# AIRZAI_BASE_BD_REVA_Sheet2.net
KiCad netlist of a schematic drawn in Altium Designer
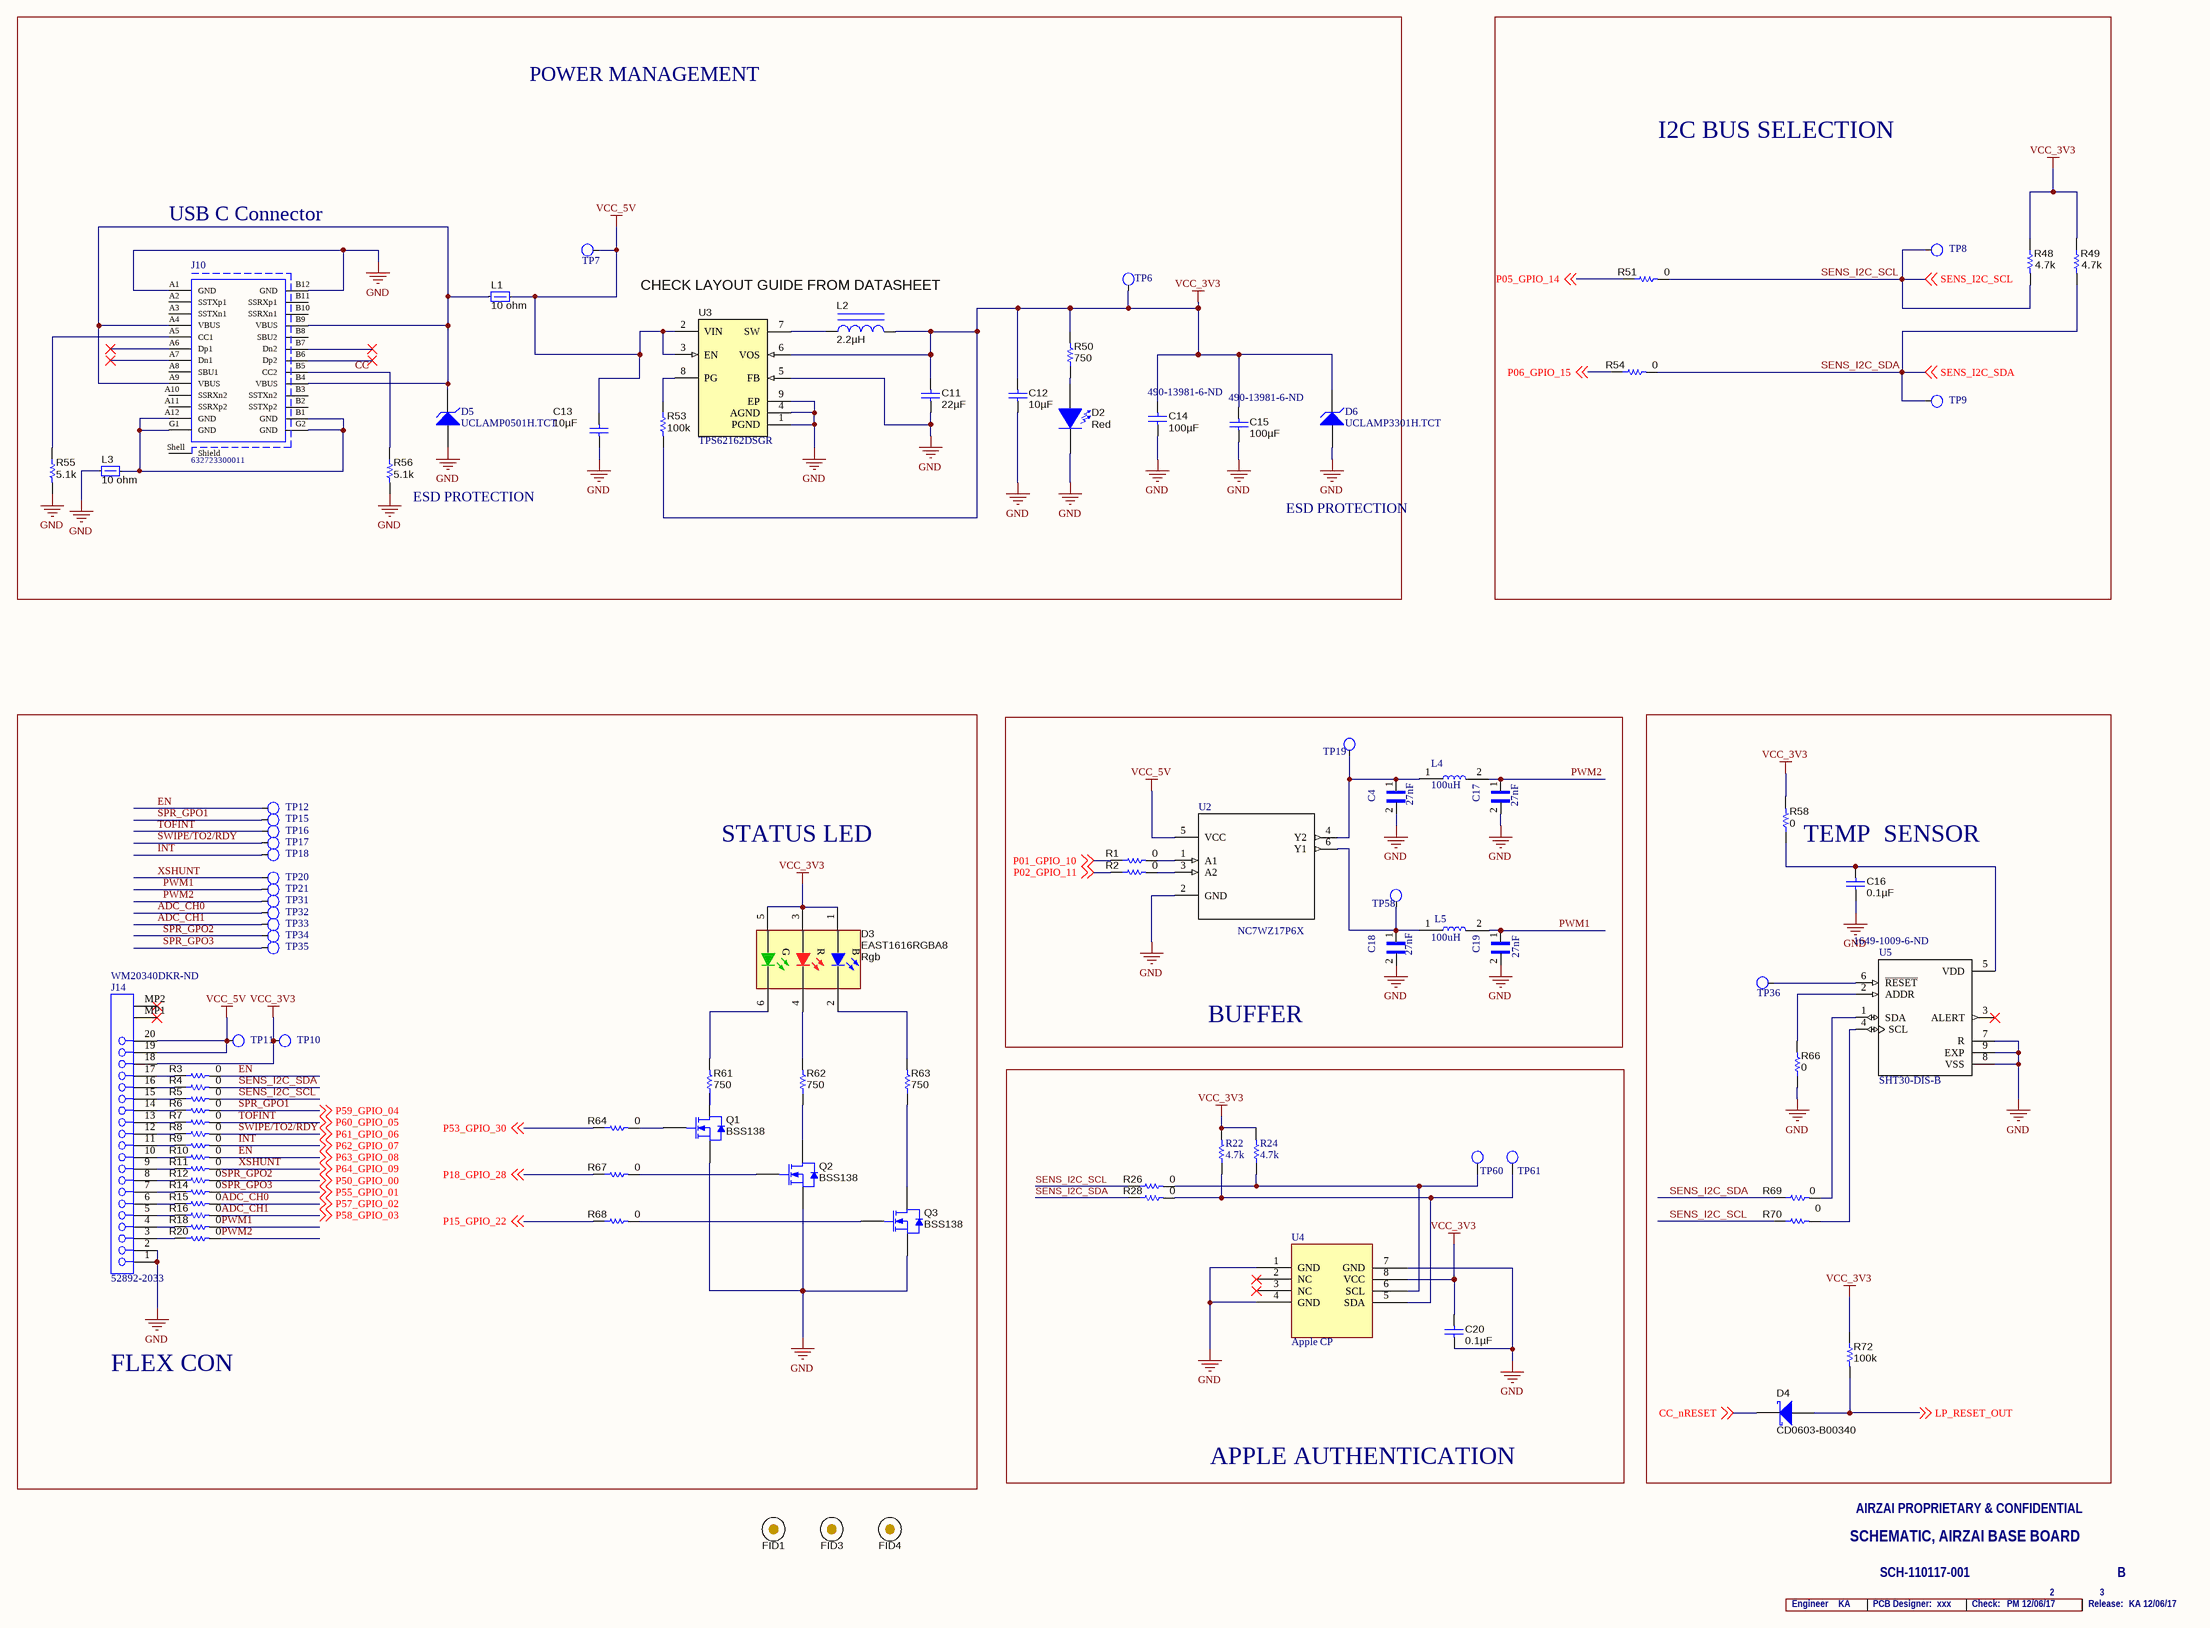
[diagram p0: AIRZAI_BASE_BD_REVA Sheet2.SchDoc]

(export (version "E")
  (design (tool "Eeschema 10.0.6"))
  (components
    (comp (ref "C4")
      (value "27nF")
      (footprint "1206CAP")
      (description "1206 27 nF 50 V Â±5% Tolerance C0G SMT Multilayer Ceramic Capacitor")
      (fields (field (name "MF") "Murata Electronics") (field (name "MP") "GRM3195C1H273JA01D"))
      (libsource (lib "GRM3195C1H273JA01D") (part "GRM3195C1H273JA01D"))
    )
    (comp (ref "C11")
      (value "C2012X5R1C226K125AC")
      (footprint "0805_HV")
      (description "CAP, CERM, 22 µF, 16 V, +/- 10%, X5R, 0805")
      (fields
        (field (name "VALUEDISPLAYED") "22µF")
        (field (name "MANUFACTURER") "TDK")
        (field (name "PUBLISHER") "Texas Instruments")
      )
      (libsource (lib "Capacitor_Ceramic") (part "C2012X5R1C226K125AC"))
    )
    (comp (ref "C12")
      (value "GRM21BR61A106KE19L")
      (footprint "0805_HV")
      (description "CAP, CERM, 10 µF, 10 V, +/- 10%, X5R, 0805")
      (fields
        (field (name "VALUEDISPLAYED") "10µF")
        (field (name "MANUFACTURER") "MuRata")
        (field (name "PUBLISHER") "Texas Instruments")
      )
      (libsource (lib "Capacitor_Ceramic") (part "GRM21BR61A106KE19L"))
    )
    (comp (ref "C13")
      (value "GRM21BR61A106KE19L")
      (footprint "0805_HV")
      (description "CAP, CERM, 10 µF, 10 V, +/- 10%, X5R, 0805")
      (fields
        (field (name "VALUEDISPLAYED") "10µF")
        (field (name "MANUFACTURER") "MuRata")
        (field (name "PUBLISHER") "Texas Instruments")
      )
      (libsource (lib "Capacitor_Ceramic") (part "GRM21BR61A106KE19L"))
    )
    (comp (ref "C14")
      (value "GRM31CR60J107ME39L")
      (footprint "1206_180")
      (description "CAP, CERM, 100 µF, 6.3 V, +/- 20%, X5R, 1206")
      (fields
        (field (name "VALUEDISPLAYED") "100µF")
        (field (name "MANUFACTURER") "MuRata")
        (field (name "SUPPLIER PART NUMBER 3") "490-13981-6-ND")
        (field (name "PUBLISHER") "Texas Instruments")
      )
      (libsource (lib "Capacitor_Ceramic") (part "GRM31CR60J107ME39L"))
    )
    (comp (ref "C15")
      (value "GRM31CR60J107ME39L")
      (footprint "1206_180")
      (description "CAP, CERM, 100 µF, 6.3 V, +/- 20%, X5R, 1206")
      (fields
        (field (name "VALUEDISPLAYED") "100µF")
        (field (name "MANUFACTURER") "MuRata")
        (field (name "SUPPLIER PART NUMBER 3") "490-13981-6-ND")
        (field (name "PUBLISHER") "Texas Instruments")
      )
      (libsource (lib "Capacitor_Ceramic") (part "GRM31CR60J107ME39L"))
    )
    (comp (ref "C16")
      (value "GRM155R61A104KA01D")
      (footprint "0402")
      (description "CAP, CERM, 0.1 µF, 10 V, +/- 10%, X5R, 0402")
      (fields
        (field (name "VALUEDISPLAYED") "0.1µF")
        (field (name "MANUFACTURER") "MuRata")
        (field (name "PUBLISHER") "Texas Instruments")
      )
      (libsource (lib "Capacitor_Ceramic") (part "GRM155R61A104KA01D"))
    )
    (comp (ref "C17")
      (value "27nF")
      (footprint "1206CAP")
      (description "1206 27 nF 50 V Â±5% Tolerance C0G SMT Multilayer Ceramic Capacitor")
      (fields (field (name "MF") "Murata Electronics") (field (name "MP") "GRM3195C1H273JA01D"))
      (libsource (lib "GRM3195C1H273JA01D") (part "GRM3195C1H273JA01D"))
    )
    (comp (ref "C18")
      (value "27nF")
      (footprint "1206CAP")
      (description "1206 27 nF 50 V Â±5% Tolerance C0G SMT Multilayer Ceramic Capacitor")
      (fields (field (name "MF") "Murata Electronics") (field (name "MP") "GRM3195C1H273JA01D"))
      (libsource (lib "GRM3195C1H273JA01D") (part "GRM3195C1H273JA01D"))
    )
    (comp (ref "C19")
      (value "27nF")
      (footprint "1206CAP")
      (description "1206 27 nF 50 V Â±5% Tolerance C0G SMT Multilayer Ceramic Capacitor")
      (fields (field (name "MF") "Murata Electronics") (field (name "MP") "GRM3195C1H273JA01D"))
      (libsource (lib "GRM3195C1H273JA01D") (part "GRM3195C1H273JA01D"))
    )
    (comp (ref "C20")
      (value "C1005X5R1A104K050BA")
      (footprint "SM0402_BTD.1SM_ACT_H55_CAP_WSS")
      (description "CAP, CERM, 0.1 µF, 10 V, +/- 10%, X5R, 0402")
      (fields
        (field (name "MANUFACTURER") "TDK")
        (field (name "VALUEDISPLAYED") "0.1µF")
        (field (name "PUBLISHER") "Texas Instruments")
      )
      (libsource (lib "AIRZAI_MBD_REVB2") (part "C1005X5R1A104K050BA"))
    )
    (comp (ref "D2")
      (value "Red")
      (footprint "SML-31_Red")
      (description "LED, Red, SMD")
      (fields
        (field (name "MANUFACTURER") "Rohm")
        (field (name "PARTNUMBER") "SML-311UTT86")
        (field (name "PUBLISHER") "Texas Instruments")
      )
      (libsource (lib "LED") (part "SML-311UTT86"))
    )
    (comp (ref "D3")
      (value "EAST1616RGBA8")
      (footprint "EAST1616_RGB")
      (description "LED, Rgb, SMD")
      (fields
        (field (name "ALTIUM_VALUE") "Rgb")
        (field (name "MANUFACTURER") "Everlight")
        (field (name "SYMBOLCREATOR") "Altium")
        (field (name "PUBLISHER") "Texas Instruments")
      )
      (libsource (lib "LED") (part "EAST1616RGBA8"))
    )
    (comp (ref "D4")
      (value "CD0603-B00340")
      (footprint "Diode_0603")
      (description "Diode, Schottky, 45 V, 0.03 A, 0603 Diode")
      (fields (field (name "MANUFACTURER") "Bourns") (field (name "PUBLISHER") "Texas Instruments"))
      (libsource (lib "Diode") (part "CD0603-B00340"))
    )
    (comp (ref "D5")
      (value "UCLAMP0501H.TCT")
      (footprint "SOD-523")
      (description "TVS DIODE 5V 12.5V SOD523")
      (fields (field (name "MANUFACTURER") "Semtech"))
      (libsource (lib "AIRZAI_BASE_BD_REVA") (part "UCLAMP0501H.TCT"))
    )
    (comp (ref "D6")
      (value "UCLAMP3301H.TCT")
      (footprint "SOD-523")
      (description "TVS DIODE 3.3V 8V SOD523")
      (fields (field (name "MANUFACTURER") "Semtech"))
      (libsource (lib "AIRZAI_BASE_BD_REVA") (part "UCLAMP3301H.TCT"))
    )
    (comp (ref "FID1")
      (value "Fiducial")
      (footprint "Fiducial10-20")
      (description "Fiducial mark.  There is nothing to buy or mount.")
      (fields (field (name "SYMBOLCREATOR") "codlsc") (field (name "PUBLISHER") "Texas Instruments"))
      (libsource (lib "MiscParts") (part "Fiducial"))
    )
    (comp (ref "FID3")
      (value "Fiducial")
      (footprint "Fiducial10-20")
      (description "Fiducial mark.  There is nothing to buy or mount.")
      (fields (field (name "SYMBOLCREATOR") "codlsc") (field (name "PUBLISHER") "Texas Instruments"))
      (libsource (lib "MiscParts") (part "Fiducial"))
    )
    (comp (ref "FID4")
      (value "Fiducial")
      (footprint "Fiducial10-20")
      (description "Fiducial mark.  There is nothing to buy or mount.")
      (fields (field (name "SYMBOLCREATOR") "codlsc") (field (name "PUBLISHER") "Texas Instruments"))
      (libsource (lib "MiscParts") (part "Fiducial"))
    )
    (comp (ref "J10")
      (value "632723300011")
      (footprint "632723300011")
      (description "USB 3.1 Type C Receptacle WR-COM, Horizontal, SMT / THT")
      (fields (field (name "PUBLISHER") "Wurth Elektronik"))
      (libsource (lib "Altium_WR-COM_USB-Connectors (rev18b)") (part "632723300011"))
    )
    (comp (ref "J14")
      (value "52892-2033")
      (footprint "MOLX-52892-2033")
      (fields (field (name "MANUFACTURER") "Molex") (field (name "SUPPLIER PART NUMBER 1") "WM20340DKR-ND"))
      (libsource (lib "Altium Content Vault") (part "MOLX-52892-2033"))
    )
    (comp (ref "L1")
      (value "10 ohm")
      (footprint "0402")
      (description "Ferrite Bead, 10 ohm @ 100 MHz, 1 A, 0402")
      (fields
        (field (name "PARTNUMBER") "BLM15AG100SN1D")
        (field (name "MANUFACTURER") "MuRata")
        (field (name "PUBLISHER") "Texas Instruments")
      )
      (libsource (lib "FerriteBead") (part "BLM15AG100SN1D"))
    )
    (comp (ref "L2")
      (value "BRC2012T2R2MD")
      (footprint "0805_HV")
      (description "Inductor, Wirewound, 2.2 µH, 1 A, 0.143 ohm, SMD")
      (fields
        (field (name "VALUEDISPLAYED") "2.2µH")
        (field (name "MANUFACTURER") "Taiyo Yuden")
        (field (name "PUBLISHER") "Texas Instruments")
      )
      (libsource (lib "Inductor_Other") (part "BRC2012T2R2MD"))
    )
    (comp (ref "L3")
      (value "10 ohm")
      (footprint "0402")
      (description "Ferrite Bead, 10 ohm @ 100 MHz, 1 A, 0402")
      (fields
        (field (name "PARTNUMBER") "BLM15AG100SN1D")
        (field (name "MANUFACTURER") "MuRata")
        (field (name "PUBLISHER") "Texas Instruments")
      )
      (libsource (lib "") (part "BLM15AG100SN1D_1"))
    )
    (comp (ref "L4")
      (value "100uH")
      (footprint "0805_Inductor")
      (description "Fixed Ind 100uh 2ma 3.1 Ohm Smd")
      (fields (field (name "MP") "MLF2012C101KTD25") (field (name "MF") "TDK"))
      (libsource (lib "MLF2012C101KTD25") (part "MLF2012C101KTD25"))
    )
    (comp (ref "L5")
      (value "100uH")
      (footprint "0805_Inductor")
      (description "Fixed Ind 100uh 2ma 3.1 Ohm Smd")
      (fields (field (name "MP") "MLF2012C101KTD25") (field (name "MF") "TDK"))
      (libsource (lib "MLF2012C101KTD25") (part "MLF2012C101KTD25"))
    )
    (comp (ref "Q1")
      (value "BSS138")
      (footprint "SOT-23")
      (description "MOSFET, N-CH, 50 V, 0.22 A, SOT-23")
      (fields
        (field (name "MANUFACTURER") "Fairchild Semiconductor")
        (field (name "PUBLISHER") "Texas Instruments")
      )
      (libsource (lib "FETs") (part "BSS138"))
    )
    (comp (ref "Q2")
      (value "BSS138")
      (footprint "SOT-23")
      (description "MOSFET, N-CH, 50 V, 0.22 A, SOT-23")
      (fields
        (field (name "MANUFACTURER") "Fairchild Semiconductor")
        (field (name "PUBLISHER") "Texas Instruments")
      )
      (libsource (lib "FETs") (part "BSS138"))
    )
    (comp (ref "Q3")
      (value "BSS138")
      (footprint "SOT-23")
      (description "MOSFET, N-CH, 50 V, 0.22 A, SOT-23")
      (fields
        (field (name "MANUFACTURER") "Fairchild Semiconductor")
        (field (name "PUBLISHER") "Texas Instruments")
      )
      (libsource (lib "FETs") (part "BSS138"))
    )
    (comp (ref "R1")
      (value "ERJ-2GE0R00X")
      (footprint "0402")
      (description "RES, 0, 5%, 0.063 W, 0402")
      (fields
        (field (name "VALUEDISPLAYED") "0")
        (field (name "MANUFACTURER") "Panasonic")
        (field (name "DIGI-KEY_PART_NUMBER") "P0.0JCT-ND")
        (field (name "PUBLISHER") "Texas Instruments")
      )
      (libsource (lib "Resistor_0402") (part "ERJ-2GE0R00X"))
    )
    (comp (ref "R2")
      (value "ERJ-2GE0R00X")
      (footprint "0402")
      (description "RES, 0, 5%, 0.063 W, 0402")
      (fields
        (field (name "VALUEDISPLAYED") "0")
        (field (name "MANUFACTURER") "Panasonic")
        (field (name "DIGI-KEY_PART_NUMBER") "P0.0JCT-ND")
        (field (name "PUBLISHER") "Texas Instruments")
      )
      (libsource (lib "Resistor_0402") (part "ERJ-2GE0R00X"))
    )
    (comp (ref "R3")
      (value "ERJ-2GE0R00X")
      (footprint "0402")
      (description "RES, 0, 5%, 0.063 W, 0402")
      (fields
        (field (name "VALUEDISPLAYED") "0")
        (field (name "MANUFACTURER") "Panasonic")
        (field (name "PUBLISHER") "Texas Instruments")
      )
      (libsource (lib "Resistor_0402") (part "ERJ-2GE0R00X"))
    )
    (comp (ref "R4")
      (value "ERJ-2GE0R00X")
      (footprint "0402")
      (description "RES, 0, 5%, 0.063 W, 0402")
      (fields
        (field (name "VALUEDISPLAYED") "0")
        (field (name "MANUFACTURER") "Panasonic")
        (field (name "PUBLISHER") "Texas Instruments")
      )
      (libsource (lib "Resistor_0402") (part "ERJ-2GE0R00X"))
    )
    (comp (ref "R5")
      (value "ERJ-2GE0R00X")
      (footprint "0402")
      (description "RES, 0, 5%, 0.063 W, 0402")
      (fields
        (field (name "VALUEDISPLAYED") "0")
        (field (name "MANUFACTURER") "Panasonic")
        (field (name "PUBLISHER") "Texas Instruments")
      )
      (libsource (lib "Resistor_0402") (part "ERJ-2GE0R00X"))
    )
    (comp (ref "R6")
      (value "ERJ-2GE0R00X")
      (footprint "0402")
      (description "RES, 0, 5%, 0.063 W, 0402")
      (fields
        (field (name "VALUEDISPLAYED") "0")
        (field (name "MANUFACTURER") "Panasonic")
        (field (name "PUBLISHER") "Texas Instruments")
      )
      (libsource (lib "Resistor_0402") (part "ERJ-2GE0R00X"))
    )
    (comp (ref "R7")
      (value "ERJ-2GE0R00X")
      (footprint "0402")
      (description "RES, 0, 5%, 0.063 W, 0402")
      (fields
        (field (name "VALUEDISPLAYED") "0")
        (field (name "MANUFACTURER") "Panasonic")
        (field (name "PUBLISHER") "Texas Instruments")
      )
      (libsource (lib "Resistor_0402") (part "ERJ-2GE0R00X"))
    )
    (comp (ref "R8")
      (value "ERJ-2GE0R00X")
      (footprint "0402")
      (description "RES, 0, 5%, 0.063 W, 0402")
      (fields
        (field (name "VALUEDISPLAYED") "0")
        (field (name "MANUFACTURER") "Panasonic")
        (field (name "PUBLISHER") "Texas Instruments")
      )
      (libsource (lib "Resistor_0402") (part "ERJ-2GE0R00X"))
    )
    (comp (ref "R9")
      (value "ERJ-2GE0R00X")
      (footprint "0402")
      (description "RES, 0, 5%, 0.063 W, 0402")
      (fields
        (field (name "VALUEDISPLAYED") "0")
        (field (name "MANUFACTURER") "Panasonic")
        (field (name "PUBLISHER") "Texas Instruments")
      )
      (libsource (lib "Resistor_0402") (part "ERJ-2GE0R00X"))
    )
    (comp (ref "R10")
      (value "ERJ-2GE0R00X")
      (footprint "0402")
      (description "RES, 0, 5%, 0.063 W, 0402")
      (fields
        (field (name "VALUEDISPLAYED") "0")
        (field (name "MANUFACTURER") "Panasonic")
        (field (name "PUBLISHER") "Texas Instruments")
      )
      (libsource (lib "Resistor_0402") (part "ERJ-2GE0R00X"))
    )
    (comp (ref "R11")
      (value "ERJ-2GE0R00X")
      (footprint "0402")
      (description "RES, 0, 5%, 0.063 W, 0402")
      (fields
        (field (name "VALUEDISPLAYED") "0")
        (field (name "MANUFACTURER") "Panasonic")
        (field (name "PUBLISHER") "Texas Instruments")
      )
      (libsource (lib "Resistor_0402") (part "ERJ-2GE0R00X"))
    )
    (comp (ref "R12")
      (value "ERJ-2GE0R00X")
      (footprint "0402")
      (description "RES, 0, 5%, 0.063 W, 0402")
      (fields
        (field (name "VALUEDISPLAYED") "0")
        (field (name "MANUFACTURER") "Panasonic")
        (field (name "PUBLISHER") "Texas Instruments")
      )
      (libsource (lib "Resistor_0402") (part "ERJ-2GE0R00X"))
    )
    (comp (ref "R14")
      (value "ERJ-2GE0R00X")
      (footprint "0402")
      (description "RES, 0, 5%, 0.063 W, 0402")
      (fields
        (field (name "VALUEDISPLAYED") "0")
        (field (name "MANUFACTURER") "Panasonic")
        (field (name "PUBLISHER") "Texas Instruments")
      )
      (libsource (lib "Resistor_0402") (part "ERJ-2GE0R00X"))
    )
    (comp (ref "R15")
      (value "ERJ-2GE0R00X")
      (footprint "0402")
      (description "RES, 0, 5%, 0.063 W, 0402")
      (fields
        (field (name "VALUEDISPLAYED") "0")
        (field (name "MANUFACTURER") "Panasonic")
        (field (name "PUBLISHER") "Texas Instruments")
      )
      (libsource (lib "Resistor_0402") (part "ERJ-2GE0R00X"))
    )
    (comp (ref "R16")
      (value "ERJ-2GE0R00X")
      (footprint "0402")
      (description "RES, 0, 5%, 0.063 W, 0402")
      (fields
        (field (name "VALUEDISPLAYED") "0")
        (field (name "MANUFACTURER") "Panasonic")
        (field (name "PUBLISHER") "Texas Instruments")
      )
      (libsource (lib "Resistor_0402") (part "ERJ-2GE0R00X"))
    )
    (comp (ref "R18")
      (value "ERJ-2GE0R00X")
      (footprint "0402")
      (description "RES, 0, 5%, 0.063 W, 0402")
      (fields
        (field (name "VALUEDISPLAYED") "0")
        (field (name "MANUFACTURER") "Panasonic")
        (field (name "PUBLISHER") "Texas Instruments")
      )
      (libsource (lib "Resistor_0402") (part "ERJ-2GE0R00X"))
    )
    (comp (ref "R20")
      (value "ERJ-2GE0R00X")
      (footprint "0402")
      (description "RES, 0, 5%, 0.063 W, 0402")
      (fields
        (field (name "VALUEDISPLAYED") "0")
        (field (name "MANUFACTURER") "Panasonic")
        (field (name "PUBLISHER") "Texas Instruments")
      )
      (libsource (lib "Resistor_0402") (part "ERJ-2GE0R00X"))
    )
    (comp (ref "R22")
      (value "RMCF0402JT4K70")
      (footprint "0402")
      (description "Chip Resistor, 4.7 KOhm, +/- 5%, 0.063 W, -55 to 155 degC, 0402 (1005 Metric), RoHS, Tape and Reel")
      (fields
        (field (name "MANUFACTURER") "Stackpole-Electronics-Inc.")
        (field (name "TOLERANCE") "±5%")
        (field (name "RESISTANCE (OHMS)") "4.7k")
      )
      (libsource (lib "AIRZAI_BASE_BD_REVA") (part "RES-2"))
    )
    (comp (ref "R24")
      (value "RMCF0402JT4K70")
      (footprint "0402")
      (description "Chip Resistor, 4.7 KOhm, +/- 5%, 0.063 W, -55 to 155 degC, 0402 (1005 Metric), RoHS, Tape and Reel")
      (fields
        (field (name "MANUFACTURER") "Stackpole-Electronics-Inc.")
        (field (name "TOLERANCE") "±5%")
        (field (name "RESISTANCE (OHMS)") "4.7k")
      )
      (libsource (lib "AIRZAI_BASE_BD_REVA") (part "RES-2"))
    )
    (comp (ref "R26")
      (value "ERJ-2GE0R00X")
      (footprint "0402")
      (description "RES, 0, 5%, 0.063 W, 0402")
      (fields
        (field (name "VALUEDISPLAYED") "0")
        (field (name "MANUFACTURER") "Panasonic")
        (field (name "DIGI-KEY_PART_NUMBER") "P0.0JCT-ND")
        (field (name "PUBLISHER") "Texas Instruments")
      )
      (libsource (lib "Resistor_0402") (part "ERJ-2GE0R00X"))
    )
    (comp (ref "R28")
      (value "ERJ-2GE0R00X")
      (footprint "0402")
      (description "RES, 0, 5%, 0.063 W, 0402")
      (fields
        (field (name "VALUEDISPLAYED") "0")
        (field (name "MANUFACTURER") "Panasonic")
        (field (name "DIGI-KEY_PART_NUMBER") "P0.0JCT-ND")
        (field (name "PUBLISHER") "Texas Instruments")
      )
      (libsource (lib "Resistor_0402") (part "ERJ-2GE0R00X"))
    )
    (comp (ref "R48")
      (value "4.7k")
      (footprint "0402")
      (description "RES SMD 4.7K OHM 1% 1/16W 0402")
      (fields
        (field (name "MANUFACTURER") "Yageo")
        (field (name "MANUFACTURER PART NUMBER") "RC0402FR-074K7L")
      )
      (libsource (lib "Resistor_0402") (part "CRCW04023K30JNED"))
    )
    (comp (ref "R49")
      (value "4.7k")
      (footprint "0402")
      (description "RES SMD 4.7K OHM 1% 1/16W 0402")
      (fields
        (field (name "MANUFACTURER") "Yageo")
        (field (name "MANUFACTURER PART NUMBER") "RC0402FR-074K7L")
      )
      (libsource (lib "Resistor_0402") (part "CRCW04023K30JNED"))
    )
    (comp (ref "R50")
      (value "RC0603JR-07750RL")
      (footprint "0603")
      (description "RES, 750, 5%, 0.1 W, 0603")
      (fields
        (field (name "VALUEDISPLAYED") "750")
        (field (name "MANUFACTURER") "Yageo America")
        (field (name "PUBLISHER") "Texas Instruments")
      )
      (libsource (lib "Resistor_0603") (part "RC0603JR-07750RL"))
    )
    (comp (ref "R51")
      (value "ERJ-2GE0R00X")
      (footprint "0402")
      (description "RES, 0, 5%, 0.063 W, 0402")
      (fields
        (field (name "VALUEDISPLAYED") "0")
        (field (name "MANUFACTURER") "Panasonic")
        (field (name "PUBLISHER") "Texas Instruments")
      )
      (libsource (lib "Resistor_0402") (part "ERJ-2GE0R00X"))
    )
    (comp (ref "R53")
      (value "CRCW0402100KJNED")
      (footprint "0402")
      (description "RES, 100 k, 5%, 0.063 W, 0402")
      (fields
        (field (name "VALUEDISPLAYED") "100k")
        (field (name "MANUFACTURER") "Vishay-Dale")
        (field (name "PUBLISHER") "Texas Instruments")
      )
      (libsource (lib "Resistor_0402") (part "CRCW0402100KJNED"))
    )
    (comp (ref "R54")
      (value "ERJ-2GE0R00X")
      (footprint "0402")
      (description "RES, 0, 5%, 0.063 W, 0402")
      (fields
        (field (name "VALUEDISPLAYED") "0")
        (field (name "MANUFACTURER") "Panasonic")
        (field (name "PUBLISHER") "Texas Instruments")
      )
      (libsource (lib "Resistor_0402") (part "ERJ-2GE0R00X"))
    )
    (comp (ref "R55")
      (value "CRCW040210K0JNED")
      (footprint "0402")
      (description "RES, 10 k, 5%, 0.063 W, 0402")
      (fields
        (field (name "VALUEDISPLAYED") "5.1k")
        (field (name "MANUFACTURER") "Vishay-Dale")
        (field (name "PUBLISHER") "Texas Instruments")
      )
      (libsource (lib "Resistor_0402") (part "CRCW040210K0JNED"))
    )
    (comp (ref "R56")
      (value "CRCW040210K0JNED")
      (footprint "0402")
      (description "RES, 10 k, 5%, 0.063 W, 0402")
      (fields
        (field (name "VALUEDISPLAYED") "5.1k")
        (field (name "MANUFACTURER") "Vishay-Dale")
        (field (name "PUBLISHER") "Texas Instruments")
      )
      (libsource (lib "Resistor_0402") (part "CRCW040210K0JNED"))
    )
    (comp (ref "R58")
      (value "ERJ-2GE0R00X")
      (footprint "0402")
      (description "RES, 0, 5%, 0.063 W, 0402")
      (fields
        (field (name "VALUEDISPLAYED") "0")
        (field (name "MANUFACTURER") "Panasonic")
        (field (name "PUBLISHER") "Texas Instruments")
      )
      (libsource (lib "Resistor_0402") (part "ERJ-2GE0R00X"))
    )
    (comp (ref "R61")
      (value "RC0603JR-07750RL")
      (footprint "0603")
      (description "RES, 750, 5%, 0.1 W, 0603")
      (fields
        (field (name "VALUEDISPLAYED") "750")
        (field (name "MANUFACTURER") "Yageo America")
        (field (name "PUBLISHER") "Texas Instruments")
      )
      (libsource (lib "Resistor_0603") (part "RC0603JR-07750RL"))
    )
    (comp (ref "R62")
      (value "RC0603JR-07750RL")
      (footprint "0603")
      (description "RES, 750, 5%, 0.1 W, 0603")
      (fields
        (field (name "VALUEDISPLAYED") "750")
        (field (name "MANUFACTURER") "Yageo America")
        (field (name "PUBLISHER") "Texas Instruments")
      )
      (libsource (lib "Resistor_0603") (part "RC0603JR-07750RL"))
    )
    (comp (ref "R63")
      (value "RC0603JR-07750RL")
      (footprint "0603")
      (description "RES, 750, 5%, 0.1 W, 0603")
      (fields
        (field (name "VALUEDISPLAYED") "750")
        (field (name "MANUFACTURER") "Yageo America")
        (field (name "PUBLISHER") "Texas Instruments")
      )
      (libsource (lib "Resistor_0603") (part "RC0603JR-07750RL"))
    )
    (comp (ref "R64")
      (value "ERJ-2GE0R00X")
      (footprint "0402")
      (description "RES, 0, 5%, 0.063 W, 0402")
      (fields
        (field (name "VALUEDISPLAYED") "0")
        (field (name "MANUFACTURER") "Panasonic")
        (field (name "PUBLISHER") "Texas Instruments")
      )
      (libsource (lib "Resistor_0402") (part "ERJ-2GE0R00X"))
    )
    (comp (ref "R66")
      (value "ERJ-2GE0R00X")
      (footprint "0402")
      (description "RES, 0, 5%, 0.063 W, 0402")
      (fields
        (field (name "VALUEDISPLAYED") "0")
        (field (name "MANUFACTURER") "Panasonic")
        (field (name "PUBLISHER") "Texas Instruments")
      )
      (libsource (lib "Resistor_0402") (part "ERJ-2GE0R00X"))
    )
    (comp (ref "R67")
      (value "ERJ-2GE0R00X")
      (footprint "0402")
      (description "RES, 0, 5%, 0.063 W, 0402")
      (fields
        (field (name "VALUEDISPLAYED") "0")
        (field (name "MANUFACTURER") "Panasonic")
        (field (name "PUBLISHER") "Texas Instruments")
      )
      (libsource (lib "Resistor_0402") (part "ERJ-2GE0R00X"))
    )
    (comp (ref "R68")
      (value "ERJ-2GE0R00X")
      (footprint "0402")
      (description "RES, 0, 5%, 0.063 W, 0402")
      (fields
        (field (name "VALUEDISPLAYED") "0")
        (field (name "MANUFACTURER") "Panasonic")
        (field (name "PUBLISHER") "Texas Instruments")
      )
      (libsource (lib "Resistor_0402") (part "ERJ-2GE0R00X"))
    )
    (comp (ref "R69")
      (value "ERJ-2GE0R00X")
      (footprint "0402")
      (description "RES, 0, 5%, 0.063 W, 0402")
      (fields
        (field (name "VALUEDISPLAYED") "0")
        (field (name "MANUFACTURER") "Panasonic")
        (field (name "PUBLISHER") "Texas Instruments")
      )
      (libsource (lib "Resistor_0402") (part "ERJ-2GE0R00X"))
    )
    (comp (ref "R70")
      (value "ERJ-2GE0R00X")
      (footprint "0402")
      (description "RES, 0, 5%, 0.063 W, 0402")
      (fields
        (field (name "VALUEDISPLAYED") "0")
        (field (name "MANUFACTURER") "Panasonic")
        (field (name "PUBLISHER") "Texas Instruments")
      )
      (libsource (lib "Resistor_0402") (part "ERJ-2GE0R00X"))
    )
    (comp (ref "R72")
      (value "CRCW0402100KJNED")
      (footprint "0402")
      (description "RES, 100 k, 5%, 0.063 W, 0402")
      (fields
        (field (name "VALUEDISPLAYED") "100k")
        (field (name "MANUFACTURER") "Vishay-Dale")
        (field (name "PUBLISHER") "Texas Instruments")
      )
      (libsource (lib "Resistor_0402") (part "CRCW0402100KJNED"))
    )
    (comp (ref "TP6")
      (value "WIREPT")
      (footprint "TP_0.9MM")
      (libsource (lib "EAGLE_CAD_Library") (part "WIREPT"))
    )
    (comp (ref "TP7")
      (value "WIREPT")
      (footprint "TP_0.9MM")
      (libsource (lib "EAGLE_CAD_Library") (part "WIREPT"))
    )
    (comp (ref "TP8")
      (value "WIREPT")
      (footprint "TP_0.9MM")
      (libsource (lib "EAGLE_CAD_Library") (part "WIREPT"))
    )
    (comp (ref "TP9")
      (value "WIREPT")
      (footprint "TP_0.9MM")
      (libsource (lib "EAGLE_CAD_Library") (part "WIREPT"))
    )
    (comp (ref "TP10")
      (value "WIREPT")
      (footprint "TP_0.9MM")
      (libsource (lib "EAGLE_CAD_Library") (part "WIREPT"))
    )
    (comp (ref "TP11")
      (value "WIREPT")
      (footprint "TP_0.9MM")
      (libsource (lib "EAGLE_CAD_Library") (part "WIREPT"))
    )
    (comp (ref "TP12")
      (value "WIREPT")
      (footprint "TP_0.9MM")
      (libsource (lib "EAGLE_CAD_Library") (part "WIREPT"))
    )
    (comp (ref "TP15")
      (value "WIREPT")
      (footprint "TP_0.9MM")
      (libsource (lib "EAGLE_CAD_Library") (part "WIREPT"))
    )
    (comp (ref "TP16")
      (value "WIREPT")
      (footprint "TP_0.9MM")
      (libsource (lib "EAGLE_CAD_Library") (part "WIREPT"))
    )
    (comp (ref "TP17")
      (value "WIREPT")
      (footprint "TP_0.9MM")
      (libsource (lib "EAGLE_CAD_Library") (part "WIREPT"))
    )
    (comp (ref "TP18")
      (value "WIREPT")
      (footprint "TP_0.9MM")
      (libsource (lib "EAGLE_CAD_Library") (part "WIREPT"))
    )
    (comp (ref "TP19")
      (value "WIREPT")
      (footprint "TP_0.9MM")
      (libsource (lib "AIRZAI_MBD_REVB") (part "WIREPT"))
    )
    (comp (ref "TP20")
      (value "WIREPT")
      (footprint "TP_0.9MM")
      (libsource (lib "EAGLE_CAD_Library") (part "WIREPT"))
    )
    (comp (ref "TP21")
      (value "WIREPT")
      (footprint "TP_0.9MM")
      (libsource (lib "EAGLE_CAD_Library") (part "WIREPT"))
    )
    (comp (ref "TP31")
      (value "WIREPT")
      (footprint "TP_0.9MM")
      (libsource (lib "EAGLE_CAD_Library") (part "WIREPT"))
    )
    (comp (ref "TP32")
      (value "WIREPT")
      (footprint "TP_0.9MM")
      (libsource (lib "EAGLE_CAD_Library") (part "WIREPT"))
    )
    (comp (ref "TP33")
      (value "WIREPT")
      (footprint "TP_0.9MM")
      (libsource (lib "EAGLE_CAD_Library") (part "WIREPT"))
    )
    (comp (ref "TP34")
      (value "WIREPT")
      (footprint "TP_0.9MM")
      (libsource (lib "EAGLE_CAD_Library") (part "WIREPT"))
    )
    (comp (ref "TP35")
      (value "WIREPT")
      (footprint "TP_0.9MM")
      (libsource (lib "EAGLE_CAD_Library") (part "WIREPT"))
    )
    (comp (ref "TP36")
      (value "WIREPT")
      (footprint "TP_0.9MM")
      (libsource (lib "EAGLE_CAD_Library") (part "WIREPT"))
    )
    (comp (ref "TP58")
      (value "WIREPT")
      (footprint "TP_0.9MM")
      (libsource (lib "AIRZAI_MBD_REVB") (part "WIREPT"))
    )
    (comp (ref "TP60")
      (value "TESTPOINT")
      (footprint "TP_0.9MM")
      (libsource (lib "AIRZAI_LID_BD_REVA") (part "TESTPOINT"))
    )
    (comp (ref "TP61")
      (value "TESTPOINT")
      (footprint "TP_0.9MM")
      (libsource (lib "AIRZAI_LID_BD_REVA") (part "TESTPOINT"))
    )
    (comp (ref "U2")
      (value "NC7WZ17P6X")
      (footprint "SC-70-NC7WZ17P6X")
      (description "NC7WZ17 Series 5.5 V TinyLogic UHS Dual Buffer w/ Schmitt Trigger Inputs-SC-70-6")
      (fields (field (name "MF") "ON Semiconductor"))
      (libsource (lib "NC7WZ17P6X") (part "NC7WZ17P6X"))
    )
    (comp (ref "U3")
      (value "TPS62162DSGR")
      (footprint "DSG0008A")
      (fields
        (field (name "MANUFACTURER") "Texas Instruments")
        (field (name "ALTERNATE PARTNUMBER") "Equivalent")
      )
      (libsource (lib "TI Power Management Step-Down Regulator") (part "TPS62162DSGR"))
    )
    (comp (ref "U4")
      (value "Apple CP")
      (footprint "XDFN-8P-Apple")
      (description "Auth 3.0 CP")
      (fields (field (name "MP") "MFI343S00177") (field (name "MF") "Apple"))
      (libsource (lib "MFI337S3959") (part "Apple CP"))
    )
    (comp (ref "U5")
      (value "SHT30-DIS-B")
      (footprint "DFN250X250X100-9N")
      (description "SHT3x Series 5.5 V Â±3 %RH 0 to 100% Temperature and Humidity Sensor - DFN-8")
      (fields (field (name "MF") "Sensirion AG") (field (name "SUPPLIER PART NUMBER 1") "1649-1009-6-ND"))
      (libsource (lib "SHT30-DIS-B") (part "SHT30-DIS-B"))
    )
  )
  (nets
    (net (code "1") (name "/CC") (class "Default")
      (node (ref "J10") (pin "B5") (pinfunction "CC2_B5") (pintype "passive"))
      (node (ref "R56") (pin "1") (pinfunction "1_1") (pintype "passive"))
    )
    (net (code "2") (name "/PWM1") (class "Default")
      (node (ref "C19") (pin "1") (pinfunction "1_1") (pintype "passive"))
      (node (ref "L5") (pin "2") (pinfunction "2_2") (pintype "passive"))
      (node (ref "R18") (pin "2") (pinfunction "2_2") (pintype "passive"))
      (node (ref "TP21") (pin "1") (pinfunction "1_1") (pintype "passive"))
    )
    (net (code "3") (name "/PWM2") (class "Default")
      (node (ref "C17") (pin "1") (pinfunction "1_1") (pintype "passive"))
      (node (ref "L4") (pin "2") (pinfunction "2_2") (pintype "passive"))
      (node (ref "R20") (pin "2") (pinfunction "2_2") (pintype "passive"))
      (node (ref "TP31") (pin "1") (pinfunction "1_1") (pintype "passive"))
    )
    (net (code "4") (name "CC_nRESET") (class "Default")
      (node (ref "D4") (pin "1") (pinfunction "K_1") (pintype "passive"))
    )
    (net (code "5") (name "GND") (class "Default")
      (node (ref "C11") (pin "2") (pinfunction "2_2") (pintype "passive"))
      (node (ref "C12") (pin "2") (pinfunction "2_2") (pintype "passive"))
      (node (ref "C13") (pin "2") (pinfunction "2_2") (pintype "passive"))
      (node (ref "C14") (pin "2") (pinfunction "2_2") (pintype "passive"))
      (node (ref "C15") (pin "2") (pinfunction "2_2") (pintype "passive"))
      (node (ref "C16") (pin "2") (pinfunction "2_2") (pintype "passive"))
      (node (ref "C17") (pin "2") (pinfunction "2_2") (pintype "passive"))
      (node (ref "C18") (pin "2") (pinfunction "2_2") (pintype "passive"))
      (node (ref "C19") (pin "2") (pinfunction "2_2") (pintype "passive"))
      (node (ref "C20") (pin "2") (pinfunction "2_2") (pintype "passive"))
      (node (ref "C4") (pin "2") (pinfunction "2_2") (pintype "passive"))
      (node (ref "D2") (pin "1") (pinfunction "K_1") (pintype "passive"))
      (node (ref "D5") (pin "A") (pinfunction "A_A") (pintype "passive"))
      (node (ref "D6") (pin "A") (pinfunction "A_A") (pintype "passive"))
      (node (ref "J10") (pin "A1") (pinfunction "GND_A1") (pintype "passive"))
      (node (ref "J10") (pin "B12") (pinfunction "GND_B12") (pintype "passive"))
      (node (ref "J14") (pin "1") (pinfunction "1_1") (pintype "passive"))
      (node (ref "J14") (pin "2") (pinfunction "2_2") (pintype "passive"))
      (node (ref "L3") (pin "2") (pinfunction "2_2") (pintype "passive"))
      (node (ref "Q1") (pin "2") (pinfunction "S_2") (pintype "passive"))
      (node (ref "Q2") (pin "2") (pinfunction "S_2") (pintype "passive"))
      (node (ref "Q3") (pin "2") (pinfunction "S_2") (pintype "passive"))
      (node (ref "R55") (pin "2") (pinfunction "2_2") (pintype "passive"))
      (node (ref "R56") (pin "2") (pinfunction "2_2") (pintype "passive"))
      (node (ref "R66") (pin "1") (pinfunction "1_1") (pintype "passive"))
      (node (ref "U2") (pin "2") (pinfunction "GND_2") (pintype "passive"))
      (node (ref "U3") (pin "1") (pinfunction "PGND_1") (pintype "power_in"))
      (node (ref "U3") (pin "4") (pinfunction "AGND_4") (pintype "power_in"))
      (node (ref "U3") (pin "5") (pinfunction "FB_5") (pintype "input"))
      (node (ref "U3") (pin "9") (pinfunction "EP_9") (pintype "power_in"))
      (node (ref "U4") (pin "1") (pinfunction "GND_1") (pintype "passive"))
      (node (ref "U4") (pin "4") (pinfunction "GND_4") (pintype "passive"))
      (node (ref "U4") (pin "7") (pinfunction "GND_7") (pintype "passive"))
      (node (ref "U5") (pin "7") (pinfunction "R_7") (pintype "passive"))
      (node (ref "U5") (pin "8") (pinfunction "VSS_8") (pintype "passive"))
      (node (ref "U5") (pin "9") (pinfunction "EXP_9") (pintype "passive"))
    )
    (net (code "6") (name "LP_RESET_OUT") (class "Default")
      (node (ref "D4") (pin "2") (pinfunction "A_2") (pintype "passive"))
      (node (ref "R72") (pin "2") (pinfunction "2_2") (pintype "passive"))
    )
    (net (code "7") (name "Net-(D2-A)") (class "Default")
      (node (ref "D2") (pin "2") (pinfunction "A_2") (pintype "passive"))
      (node (ref "R50") (pin "1") (pinfunction "1_1") (pintype "passive"))
    )
    (net (code "8") (name "Net-(D3-K-Pad2)") (class "Default")
      (node (ref "D3") (pin "2") (pinfunction "K_2") (pintype "passive"))
      (node (ref "R63") (pin "2") (pinfunction "2_2") (pintype "passive"))
    )
    (net (code "9") (name "Net-(D3-K-Pad4)") (class "Default")
      (node (ref "D3") (pin "4") (pinfunction "K_4") (pintype "passive"))
      (node (ref "R62") (pin "2") (pinfunction "2_2") (pintype "passive"))
    )
    (net (code "10") (name "Net-(D3-K-Pad6)") (class "Default")
      (node (ref "D3") (pin "6") (pinfunction "K_6") (pintype "passive"))
      (node (ref "R61") (pin "2") (pinfunction "2_2") (pintype "passive"))
    )
    (net (code "11") (name "Net-(D5-PadK)") (class "Default")
      (node (ref "D5") (pin "K") (pinfunction "K_K") (pintype "passive"))
      (node (ref "J10") (pin "A4") (pinfunction "VBUS_A4") (pintype "passive"))
      (node (ref "J10") (pin "A9") (pinfunction "VBUS_A9") (pintype "passive"))
      (node (ref "J10") (pin "B4") (pinfunction "VBUS_B4") (pintype "passive"))
      (node (ref "J10") (pin "B9") (pinfunction "VBUS_B9") (pintype "passive"))
      (node (ref "L1") (pin "1") (pinfunction "1_1") (pintype "passive"))
    )
    (net (code "12") (name "Net-(J10-CC1)") (class "Default")
      (node (ref "J10") (pin "A5") (pinfunction "CC1_A5") (pintype "passive"))
      (node (ref "R55") (pin "1") (pinfunction "1_1") (pintype "passive"))
    )
    (net (code "13") (name "Net-(J10-GND-PadA12)") (class "Default")
      (node (ref "J10") (pin "A12") (pinfunction "GND_A12") (pintype "passive"))
      (node (ref "J10") (pin "B1") (pinfunction "GND_B1") (pintype "passive"))
      (node (ref "J10") (pin "G1") (pinfunction "GND_G1") (pintype "passive"))
      (node (ref "J10") (pin "G2") (pinfunction "GND_G2") (pintype "passive"))
      (node (ref "L3") (pin "1") (pinfunction "1_1") (pintype "passive"))
    )
    (net (code "14") (name "Net-(J14-Pad3)") (class "Default")
      (node (ref "J14") (pin "3") (pinfunction "3_3") (pintype "passive"))
      (node (ref "R20") (pin "1") (pinfunction "1_1") (pintype "passive"))
    )
    (net (code "15") (name "Net-(J14-Pad4)") (class "Default")
      (node (ref "J14") (pin "4") (pinfunction "4_4") (pintype "passive"))
      (node (ref "R18") (pin "1") (pinfunction "1_1") (pintype "passive"))
    )
    (net (code "16") (name "Net-(J14-Pad5)") (class "Default")
      (node (ref "J14") (pin "5") (pinfunction "5_5") (pintype "passive"))
      (node (ref "R16") (pin "1") (pinfunction "1_1") (pintype "passive"))
    )
    (net (code "17") (name "Net-(J14-Pad6)") (class "Default")
      (node (ref "J14") (pin "6") (pinfunction "6_6") (pintype "passive"))
      (node (ref "R15") (pin "1") (pinfunction "1_1") (pintype "passive"))
    )
    (net (code "18") (name "Net-(J14-Pad7)") (class "Default")
      (node (ref "J14") (pin "7") (pinfunction "7_7") (pintype "passive"))
      (node (ref "R14") (pin "1") (pinfunction "1_1") (pintype "passive"))
    )
    (net (code "19") (name "Net-(J14-Pad8)") (class "Default")
      (node (ref "J14") (pin "8") (pinfunction "8_8") (pintype "passive"))
      (node (ref "R12") (pin "1") (pinfunction "1_1") (pintype "passive"))
    )
    (net (code "20") (name "Net-(J14-Pad9)") (class "Default")
      (node (ref "J14") (pin "9") (pinfunction "9_9") (pintype "passive"))
      (node (ref "R11") (pin "1") (pinfunction "1_1") (pintype "passive"))
    )
    (net (code "21") (name "Net-(J14-Pad10)") (class "Default")
      (node (ref "J14") (pin "10") (pinfunction "10_10") (pintype "passive"))
      (node (ref "R10") (pin "1") (pinfunction "1_1") (pintype "passive"))
    )
    (net (code "22") (name "Net-(J14-Pad11)") (class "Default")
      (node (ref "J14") (pin "11") (pinfunction "11_11") (pintype "passive"))
      (node (ref "R9") (pin "1") (pinfunction "1_1") (pintype "passive"))
    )
    (net (code "23") (name "Net-(J14-Pad12)") (class "Default")
      (node (ref "J14") (pin "12") (pinfunction "12_12") (pintype "passive"))
      (node (ref "R8") (pin "1") (pinfunction "1_1") (pintype "passive"))
    )
    (net (code "24") (name "Net-(J14-Pad13)") (class "Default")
      (node (ref "J14") (pin "13") (pinfunction "13_13") (pintype "passive"))
      (node (ref "R7") (pin "1") (pinfunction "1_1") (pintype "passive"))
    )
    (net (code "25") (name "Net-(J14-Pad14)") (class "Default")
      (node (ref "J14") (pin "14") (pinfunction "14_14") (pintype "passive"))
      (node (ref "R6") (pin "1") (pinfunction "1_1") (pintype "passive"))
    )
    (net (code "26") (name "Net-(J14-Pad15)") (class "Default")
      (node (ref "J14") (pin "15") (pinfunction "15_15") (pintype "passive"))
      (node (ref "R5") (pin "1") (pinfunction "1_1") (pintype "passive"))
    )
    (net (code "27") (name "Net-(J14-Pad16)") (class "Default")
      (node (ref "J14") (pin "16") (pinfunction "16_16") (pintype "passive"))
      (node (ref "R4") (pin "1") (pinfunction "1_1") (pintype "passive"))
    )
    (net (code "28") (name "Net-(J14-Pad17)") (class "Default")
      (node (ref "J14") (pin "17") (pinfunction "17_17") (pintype "passive"))
      (node (ref "R3") (pin "1") (pinfunction "1_1") (pintype "passive"))
    )
    (net (code "29") (name "Net-(Q1-D)") (class "Default")
      (node (ref "Q1") (pin "3") (pinfunction "D_3") (pintype "passive"))
      (node (ref "R61") (pin "1") (pinfunction "1_1") (pintype "passive"))
    )
    (net (code "30") (name "Net-(Q1-G)") (class "Default")
      (node (ref "Q1") (pin "1") (pinfunction "G_1") (pintype "passive"))
      (node (ref "R64") (pin "2") (pinfunction "2_2") (pintype "passive"))
    )
    (net (code "31") (name "Net-(Q2-D)") (class "Default")
      (node (ref "Q2") (pin "3") (pinfunction "D_3") (pintype "passive"))
      (node (ref "R62") (pin "1") (pinfunction "1_1") (pintype "passive"))
    )
    (net (code "32") (name "Net-(Q2-G)") (class "Default")
      (node (ref "Q2") (pin "1") (pinfunction "G_1") (pintype "passive"))
      (node (ref "R67") (pin "2") (pinfunction "2_2") (pintype "passive"))
    )
    (net (code "33") (name "Net-(Q3-D)") (class "Default")
      (node (ref "Q3") (pin "3") (pinfunction "D_3") (pintype "passive"))
      (node (ref "R63") (pin "1") (pinfunction "1_1") (pintype "passive"))
    )
    (net (code "34") (name "Net-(Q3-G)") (class "Default")
      (node (ref "Q3") (pin "1") (pinfunction "G_1") (pintype "passive"))
      (node (ref "R68") (pin "2") (pinfunction "2_2") (pintype "passive"))
    )
    (net (code "35") (name "Net-(U2-A1)") (class "Default")
      (node (ref "R1") (pin "2") (pinfunction "2_2") (pintype "passive"))
      (node (ref "U2") (pin "1") (pinfunction "A1_1") (pintype "input"))
    )
    (net (code "36") (name "Net-(U2-A2)") (class "Default")
      (node (ref "R2") (pin "2") (pinfunction "2_2") (pintype "passive"))
      (node (ref "U2") (pin "3") (pinfunction "A2_3") (pintype "input"))
    )
    (net (code "37") (name "Net-(U2-Y1)") (class "Default")
      (node (ref "C18") (pin "1") (pinfunction "1_1") (pintype "passive"))
      (node (ref "L5") (pin "1") (pinfunction "1_1") (pintype "passive"))
      (node (ref "TP58") (pin "1") (pinfunction "1_1") (pintype "passive"))
      (node (ref "U2") (pin "6") (pinfunction "Y1_6") (pintype "output"))
    )
    (net (code "38") (name "Net-(U2-Y2)") (class "Default")
      (node (ref "C4") (pin "1") (pinfunction "1_1") (pintype "passive"))
      (node (ref "L4") (pin "1") (pinfunction "1_1") (pintype "passive"))
      (node (ref "TP19") (pin "1") (pinfunction "1_1") (pintype "passive"))
      (node (ref "U2") (pin "4") (pinfunction "Y2_4") (pintype "output"))
    )
    (net (code "39") (name "Net-(U3-PG)") (class "Default")
      (node (ref "R53") (pin "1") (pinfunction "1_1") (pintype "passive"))
      (node (ref "U3") (pin "8") (pinfunction "PG_8") (pintype "tri_state"))
    )
    (net (code "40") (name "Net-(U3-SW)") (class "Default")
      (node (ref "L2") (pin "1") (pinfunction "1_1") (pintype "passive"))
      (node (ref "U3") (pin "7") (pinfunction "SW_7") (pintype "power_in"))
    )
    (net (code "41") (name "Net-(U4-SCL)") (class "Default")
      (node (ref "R24") (pin "1") (pinfunction "1_1") (pintype "passive"))
      (node (ref "R26") (pin "2") (pinfunction "2_2") (pintype "passive"))
      (node (ref "TP60") (pin "1") (pinfunction "1_1") (pintype "passive"))
      (node (ref "U4") (pin "6") (pinfunction "SCL_6") (pintype "passive"))
    )
    (net (code "42") (name "Net-(U4-SDA)") (class "Default")
      (node (ref "R22") (pin "1") (pinfunction "1_1") (pintype "passive"))
      (node (ref "R28") (pin "2") (pinfunction "2_2") (pintype "passive"))
      (node (ref "TP61") (pin "1") (pinfunction "1_1") (pintype "passive"))
      (node (ref "U4") (pin "5") (pinfunction "SDA_5") (pintype "passive"))
    )
    (net (code "43") (name "Net-(U5-ADDR)") (class "Default")
      (node (ref "R66") (pin "2") (pinfunction "2_2") (pintype "passive"))
      (node (ref "U5") (pin "2") (pinfunction "ADDR_2") (pintype "input"))
    )
    (net (code "44") (name "Net-(U5-SCL)") (class "Default")
      (node (ref "R70") (pin "2") (pinfunction "2_2") (pintype "passive"))
      (node (ref "U5") (pin "4") (pinfunction "SCL_4") (pintype "bidirectional"))
    )
    (net (code "45") (name "Net-(U5-SDA)") (class "Default")
      (node (ref "R69") (pin "2") (pinfunction "2_2") (pintype "passive"))
      (node (ref "U5") (pin "1") (pinfunction "SDA_1") (pintype "bidirectional"))
    )
    (net (code "46") (name "Net-(U5-VDD)") (class "Default")
      (node (ref "C16") (pin "1") (pinfunction "1_1") (pintype "passive"))
      (node (ref "R58") (pin "1") (pinfunction "1_1") (pintype "passive"))
      (node (ref "U5") (pin "5") (pinfunction "VDD_5") (pintype "power_in"))
    )
    (net (code "47") (name "Net-(U5-~{RESET})") (class "Default")
      (node (ref "TP36") (pin "1") (pinfunction "1_1") (pintype "passive"))
      (node (ref "U5") (pin "6") (pinfunction "~{RESET}_6") (pintype "input"))
    )
    (net (code "48") (name "P01_GPIO_10") (class "Default")
      (node (ref "R1") (pin "1") (pinfunction "1_1") (pintype "passive"))
    )
    (net (code "49") (name "P02_GPIO_11") (class "Default")
      (node (ref "R2") (pin "1") (pinfunction "1_1") (pintype "passive"))
    )
    (net (code "50") (name "P05_GPIO_14") (class "Default")
      (node (ref "R51") (pin "1") (pinfunction "1_1") (pintype "passive"))
    )
    (net (code "51") (name "P06_GPIO_15") (class "Default")
      (node (ref "R54") (pin "1") (pinfunction "1_1") (pintype "passive"))
    )
    (net (code "52") (name "P15_GPIO_22") (class "Default")
      (node (ref "R68") (pin "1") (pinfunction "1_1") (pintype "passive"))
    )
    (net (code "53") (name "P18_GPIO_28") (class "Default")
      (node (ref "R67") (pin "1") (pinfunction "1_1") (pintype "passive"))
    )
    (net (code "54") (name "P50_GPIO_00") (class "Default")
      (node (ref "R12") (pin "2") (pinfunction "2_2") (pintype "passive"))
      (node (ref "TP34") (pin "1") (pinfunction "1_1") (pintype "passive"))
    )
    (net (code "55") (name "P53_GPIO_30") (class "Default")
      (node (ref "R64") (pin "1") (pinfunction "1_1") (pintype "passive"))
    )
    (net (code "56") (name "P55_GPIO_01") (class "Default")
      (node (ref "R14") (pin "2") (pinfunction "2_2") (pintype "passive"))
      (node (ref "TP35") (pin "1") (pinfunction "1_1") (pintype "passive"))
    )
    (net (code "57") (name "P57_GPIO_02") (class "Default")
      (node (ref "R15") (pin "2") (pinfunction "2_2") (pintype "passive"))
      (node (ref "TP32") (pin "1") (pinfunction "1_1") (pintype "passive"))
    )
    (net (code "58") (name "P58_GPIO_03") (class "Default")
      (node (ref "R16") (pin "2") (pinfunction "2_2") (pintype "passive"))
      (node (ref "TP33") (pin "1") (pinfunction "1_1") (pintype "passive"))
    )
    (net (code "59") (name "P59_GPIO_04") (class "Default")
      (node (ref "R6") (pin "2") (pinfunction "2_2") (pintype "passive"))
      (node (ref "TP15") (pin "1") (pinfunction "1_1") (pintype "passive"))
    )
    (net (code "60") (name "P60_GPIO_05") (class "Default")
      (node (ref "R7") (pin "2") (pinfunction "2_2") (pintype "passive"))
      (node (ref "TP16") (pin "1") (pinfunction "1_1") (pintype "passive"))
    )
    (net (code "61") (name "P61_GPIO_06") (class "Default")
      (node (ref "R8") (pin "2") (pinfunction "2_2") (pintype "passive"))
      (node (ref "TP17") (pin "1") (pinfunction "1_1") (pintype "passive"))
    )
    (net (code "62") (name "P62_GPIO_07") (class "Default")
      (node (ref "R9") (pin "2") (pinfunction "2_2") (pintype "passive"))
      (node (ref "TP18") (pin "1") (pinfunction "1_1") (pintype "passive"))
    )
    (net (code "63") (name "P63_GPIO_08") (class "Default")
      (node (ref "R10") (pin "2") (pinfunction "2_2") (pintype "passive"))
      (node (ref "R3") (pin "2") (pinfunction "2_2") (pintype "passive"))
      (node (ref "TP12") (pin "1") (pinfunction "1_1") (pintype "passive"))
    )
    (net (code "64") (name "P64_GPIO_09") (class "Default")
      (node (ref "R11") (pin "2") (pinfunction "2_2") (pintype "passive"))
      (node (ref "TP20") (pin "1") (pinfunction "1_1") (pintype "passive"))
    )
    (net (code "65") (name "SENS_I2C_SCL") (class "Default")
      (node (ref "R26") (pin "1") (pinfunction "1_1") (pintype "passive"))
      (node (ref "R48") (pin "2") (pinfunction "2_2") (pintype "passive"))
      (node (ref "R5") (pin "2") (pinfunction "2_2") (pintype "passive"))
      (node (ref "R51") (pin "2") (pinfunction "2_2") (pintype "passive"))
      (node (ref "R70") (pin "1") (pinfunction "1_1") (pintype "passive"))
      (node (ref "TP8") (pin "1") (pinfunction "1_1") (pintype "passive"))
    )
    (net (code "66") (name "SENS_I2C_SDA") (class "Default")
      (node (ref "R28") (pin "1") (pinfunction "1_1") (pintype "passive"))
      (node (ref "R4") (pin "2") (pinfunction "2_2") (pintype "passive"))
      (node (ref "R49") (pin "2") (pinfunction "2_2") (pintype "passive"))
      (node (ref "R54") (pin "2") (pinfunction "2_2") (pintype "passive"))
      (node (ref "R69") (pin "1") (pinfunction "1_1") (pintype "passive"))
      (node (ref "TP9") (pin "1") (pinfunction "1_1") (pintype "passive"))
    )
    (net (code "67") (name "VCC_3V3") (class "Default")
      (node (ref "C11") (pin "1") (pinfunction "1_1") (pintype "passive"))
      (node (ref "C12") (pin "1") (pinfunction "1_1") (pintype "passive"))
      (node (ref "C14") (pin "1") (pinfunction "1_1") (pintype "passive"))
      (node (ref "C15") (pin "1") (pinfunction "1_1") (pintype "passive"))
      (node (ref "C20") (pin "1") (pinfunction "1_1") (pintype "passive"))
      (node (ref "D3") (pin "1") (pinfunction "A_1") (pintype "passive"))
      (node (ref "D3") (pin "3") (pinfunction "A_3") (pintype "passive"))
      (node (ref "D3") (pin "5") (pinfunction "A_5") (pintype "passive"))
      (node (ref "D6") (pin "K") (pinfunction "K_K") (pintype "passive"))
      (node (ref "J14") (pin "18") (pinfunction "18_18") (pintype "passive"))
      (node (ref "L2") (pin "2") (pinfunction "2_2") (pintype "passive"))
      (node (ref "R22") (pin "2") (pinfunction "2_2") (pintype "passive"))
      (node (ref "R24") (pin "2") (pinfunction "2_2") (pintype "passive"))
      (node (ref "R48") (pin "1") (pinfunction "1_1") (pintype "passive"))
      (node (ref "R49") (pin "1") (pinfunction "1_1") (pintype "passive"))
      (node (ref "R50") (pin "2") (pinfunction "2_2") (pintype "passive"))
      (node (ref "R53") (pin "2") (pinfunction "2_2") (pintype "passive"))
      (node (ref "R58") (pin "2") (pinfunction "2_2") (pintype "passive"))
      (node (ref "R72") (pin "1") (pinfunction "1_1") (pintype "passive"))
      (node (ref "TP10") (pin "1") (pinfunction "1_1") (pintype "passive"))
      (node (ref "TP6") (pin "1") (pinfunction "1_1") (pintype "passive"))
      (node (ref "U3") (pin "6") (pinfunction "VOS_6") (pintype "input"))
      (node (ref "U4") (pin "8") (pinfunction "VCC_8") (pintype "passive"))
    )
    (net (code "68") (name "VCC_5V") (class "Default")
      (node (ref "C13") (pin "1") (pinfunction "1_1") (pintype "passive"))
      (node (ref "J14") (pin "19") (pinfunction "19_19") (pintype "passive"))
      (node (ref "J14") (pin "20") (pinfunction "20_20") (pintype "passive"))
      (node (ref "L1") (pin "2") (pinfunction "2_2") (pintype "passive"))
      (node (ref "TP11") (pin "1") (pinfunction "1_1") (pintype "passive"))
      (node (ref "TP7") (pin "1") (pinfunction "1_1") (pintype "passive"))
      (node (ref "U2") (pin "5") (pinfunction "VCC_5") (pintype "power_in"))
      (node (ref "U3") (pin "2") (pinfunction "VIN_2") (pintype "power_in"))
      (node (ref "U3") (pin "3") (pinfunction "EN_3") (pintype "input"))
    )
    (net (code "69") (name "unconnected-(J10-Dn1-PadA7)") (class "Default")
      (node (ref "J10") (pin "A7") (pinfunction "Dn1_A7") (pintype "passive+no_connect"))
    )
    (net (code "70") (name "unconnected-(J10-Dn2-PadB7)") (class "Default")
      (node (ref "J10") (pin "B7") (pinfunction "Dn2_B7") (pintype "passive+no_connect"))
    )
    (net (code "71") (name "unconnected-(J10-Dp1-PadA6)") (class "Default")
      (node (ref "J10") (pin "A6") (pinfunction "Dp1_A6") (pintype "passive+no_connect"))
    )
    (net (code "72") (name "unconnected-(J10-Dp2-PadB6)") (class "Default")
      (node (ref "J10") (pin "B6") (pinfunction "Dp2_B6") (pintype "passive+no_connect"))
    )
    (net (code "73") (name "unconnected-(J10-SBU1-PadA8)") (class "Default")
      (node (ref "J10") (pin "A8") (pinfunction "SBU1_A8") (pintype "passive"))
    )
    (net (code "74") (name "unconnected-(J10-SBU2-PadB8)") (class "Default")
      (node (ref "J10") (pin "B8") (pinfunction "SBU2_B8") (pintype "passive"))
    )
    (net (code "75") (name "unconnected-(J10-SSRXn1-PadB10)") (class "Default")
      (node (ref "J10") (pin "B10") (pinfunction "SSRXn1_B10") (pintype "passive"))
    )
    (net (code "76") (name "unconnected-(J10-SSRXn2-PadA10)") (class "Default")
      (node (ref "J10") (pin "A10") (pinfunction "SSRXn2_A10") (pintype "passive"))
    )
    (net (code "77") (name "unconnected-(J10-SSRXp1-PadB11)") (class "Default")
      (node (ref "J10") (pin "B11") (pinfunction "SSRXp1_B11") (pintype "passive"))
    )
    (net (code "78") (name "unconnected-(J10-SSRXp2-PadA11)") (class "Default")
      (node (ref "J10") (pin "A11") (pinfunction "SSRXp2_A11") (pintype "passive"))
    )
    (net (code "79") (name "unconnected-(J10-SSTXn1-PadA3)") (class "Default")
      (node (ref "J10") (pin "A3") (pinfunction "SSTXn1_A3") (pintype "passive"))
    )
    (net (code "80") (name "unconnected-(J10-SSTXn2-PadB3)") (class "Default")
      (node (ref "J10") (pin "B3") (pinfunction "SSTXn2_B3") (pintype "passive"))
    )
    (net (code "81") (name "unconnected-(J10-SSTXp1-PadA2)") (class "Default")
      (node (ref "J10") (pin "A2") (pinfunction "SSTXp1_A2") (pintype "passive"))
    )
    (net (code "82") (name "unconnected-(J10-SSTXp2-PadB2)") (class "Default")
      (node (ref "J10") (pin "B2") (pinfunction "SSTXp2_B2") (pintype "passive"))
    )
    (net (code "83") (name "unconnected-(J10-Shield-PadShell)") (class "Default")
      (node (ref "J10") (pin "Shell") (pinfunction "Shield_Shell") (pintype "passive"))
    )
    (net (code "84") (name "unconnected-(J14-PadMP1)") (class "Default")
      (node (ref "J14") (pin "MP1") (pinfunction "MP1_MP1") (pintype "passive+no_connect"))
    )
    (net (code "85") (name "unconnected-(J14-PadMP2)") (class "Default")
      (node (ref "J14") (pin "MP2") (pinfunction "MP2_MP2") (pintype "passive+no_connect"))
    )
    (net (code "86") (name "unconnected-(U4-NC-Pad2)") (class "Default")
      (node (ref "U4") (pin "2") (pinfunction "NC_2") (pintype "passive+no_connect"))
    )
    (net (code "87") (name "unconnected-(U4-NC-Pad3)") (class "Default")
      (node (ref "U4") (pin "3") (pinfunction "NC_3") (pintype "passive+no_connect"))
    )
    (net (code "88") (name "unconnected-(U5-ALERT-Pad3)") (class "Default")
      (node (ref "U5") (pin "3") (pinfunction "ALERT_3") (pintype "output+no_connect"))
    )
  )
)
